# SCH_UART-HMI-OLED_2026-03-10.net
KiCad netlist of a schematic drawn in EasyEDA
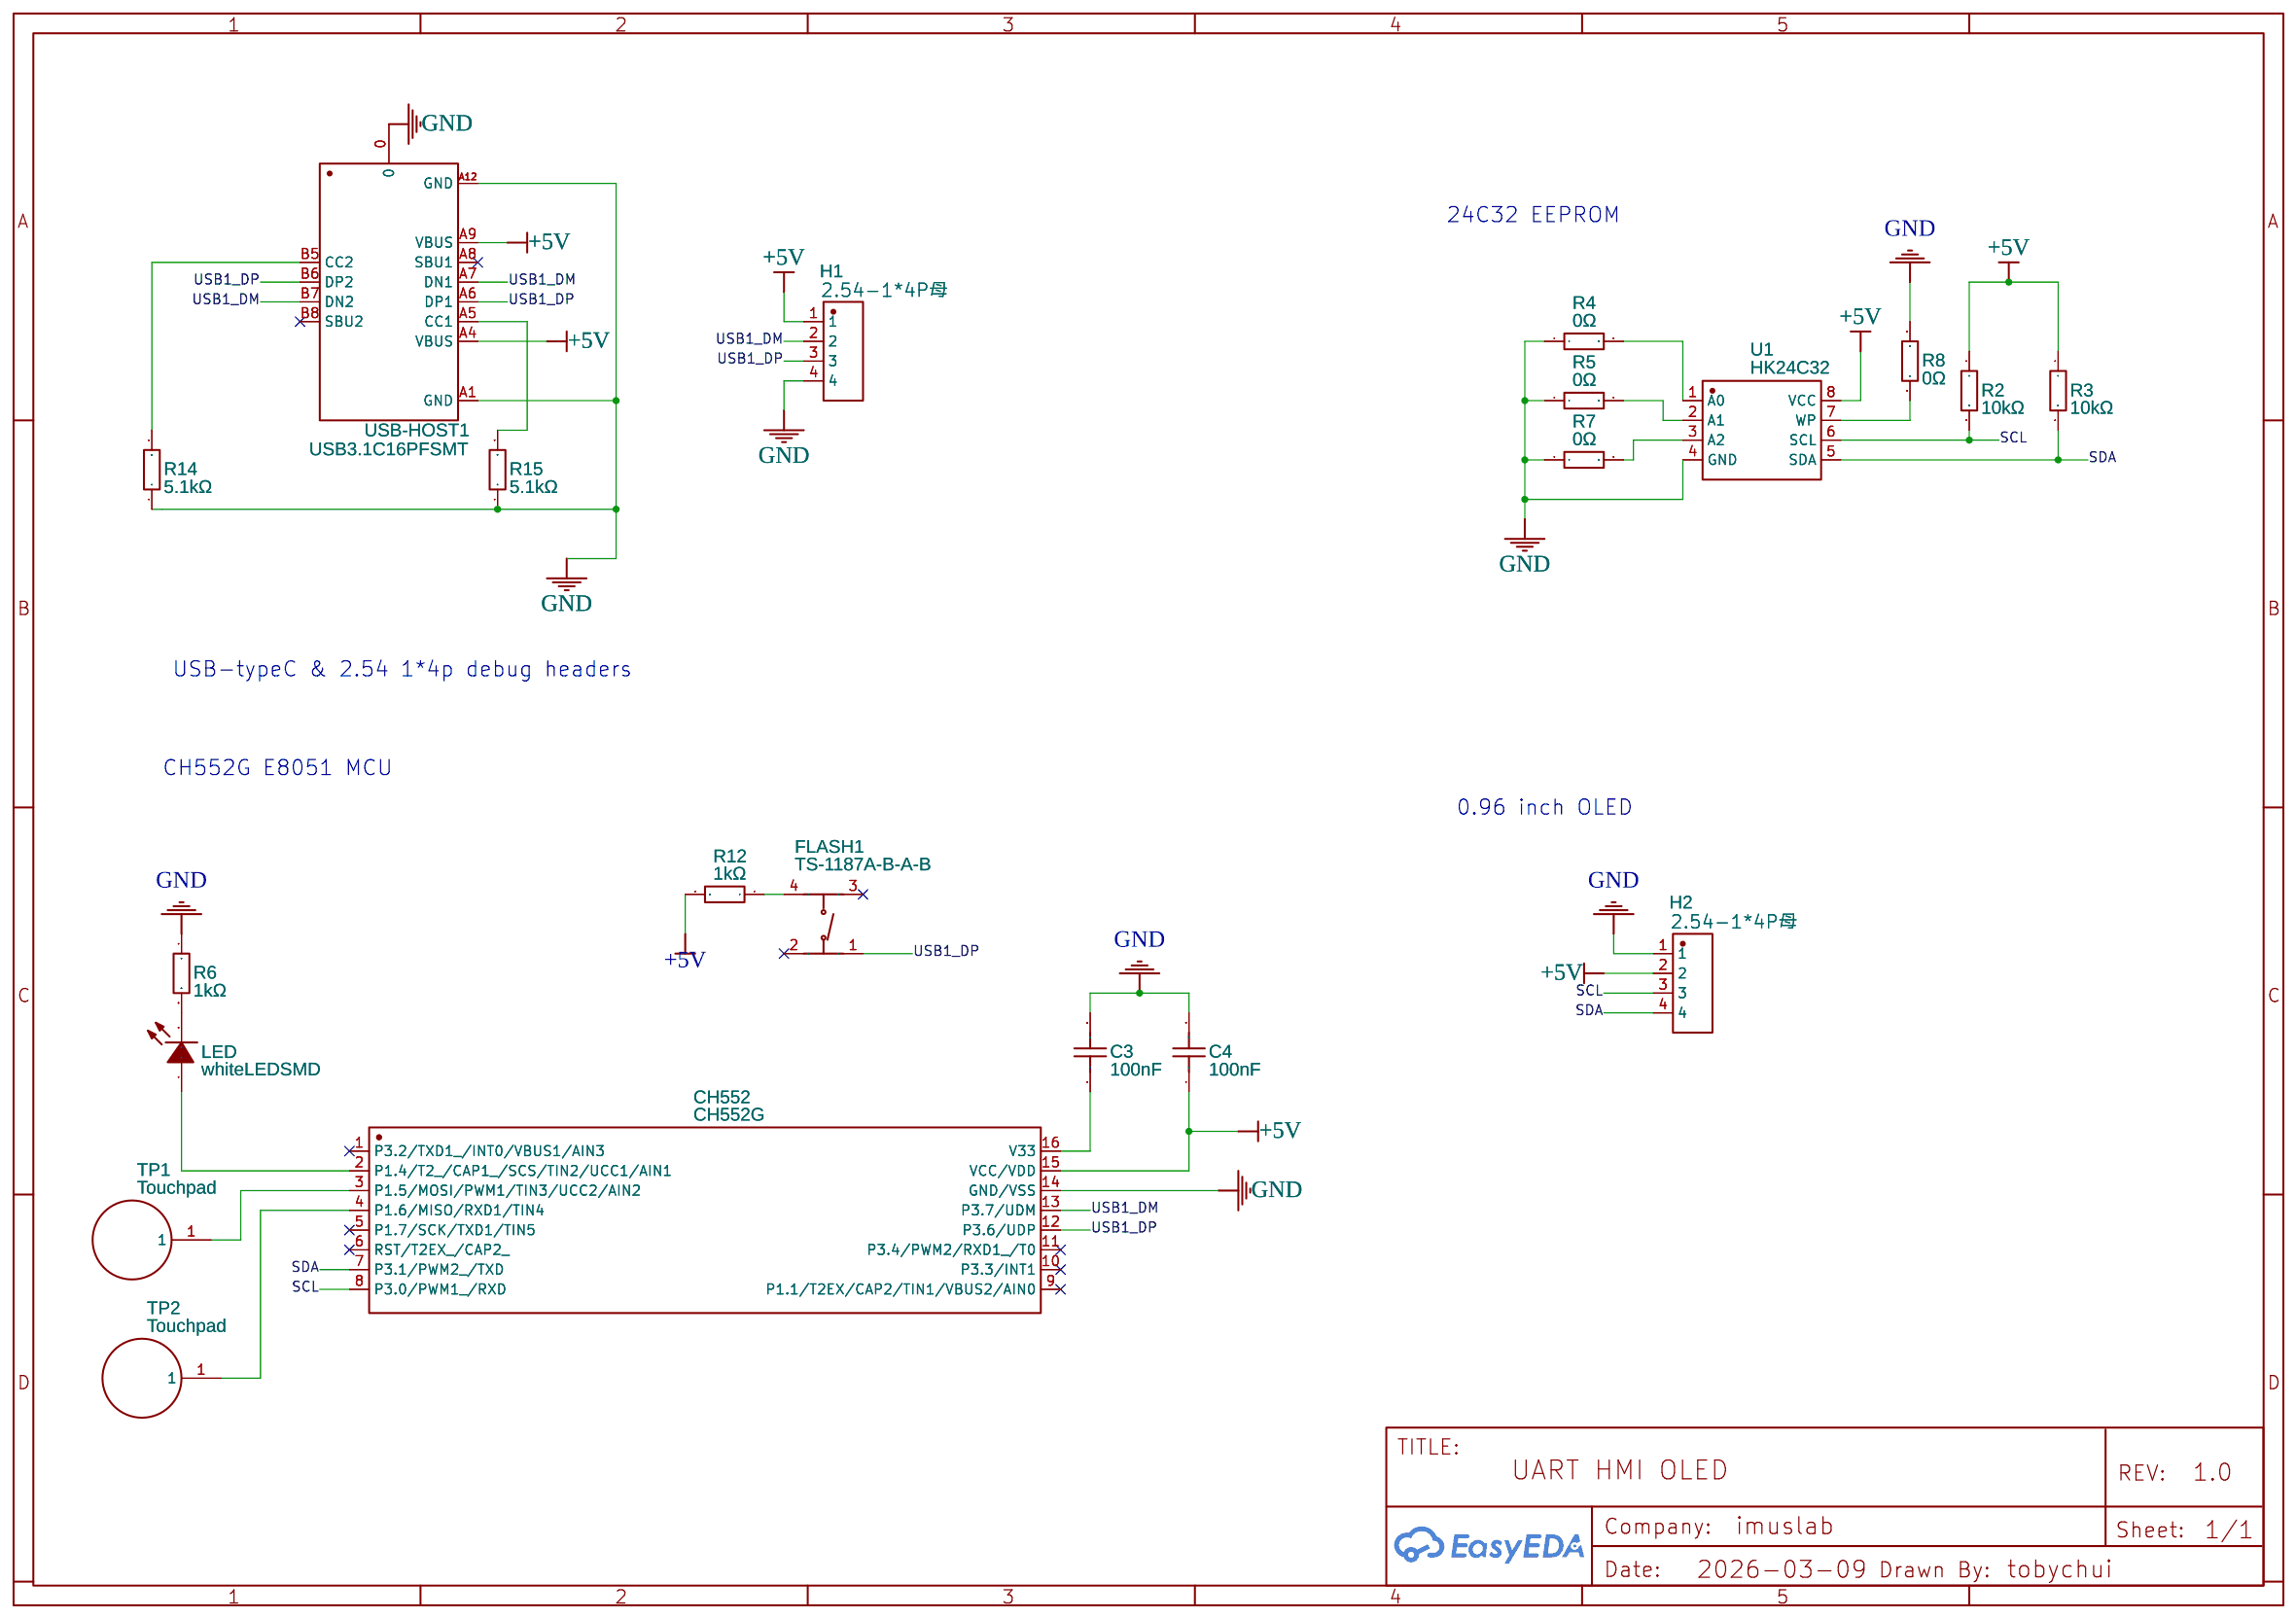
[diagram p0: schematic sheet]

(export (version "E")
  (design (tool "Eeschema 10.0.6"))
  (components
    (comp (ref "C3")
      (value "100nF")
      (fields
        (field (name "Manufacturer Part") "CC0805KRX7R9BB104")
        (field (name "Manufacturer") "YAGEO(国巨)")
      )
      (libsource (lib "") (part "CC0805KRX7R9BB104"))
    )
    (comp (ref "C4")
      (value "100nF")
      (fields
        (field (name "Manufacturer Part") "CC0805KRX7R9BB104")
        (field (name "Manufacturer") "YAGEO(国巨)")
      )
      (libsource (lib "") (part "CC0805KRX7R9BB104"))
    )
    (comp (ref "CH552")
      (value "CH552G")
      (fields (field (name "Manufacturer") "WCH(南京沁恒)"))
      (libsource (lib "") (part "CH552G"))
    )
    (comp (ref "FLASH1")
      (value "TS-1187A-B-A-B")
      (fields (field (name "Manufacturer") "XKB Connectivity(中国星坤)"))
      (libsource (lib "") (part "TS-1187A-B-A-B"))
    )
    (comp (ref "H1")
      (value "2.54-1*4P母")
      (fields (field (name "Manufacturer") "BOOMELE(博穆精密)"))
      (libsource (lib "") (part "2.54-1*4P母"))
    )
    (comp (ref "H2")
      (value "2.54-1*4P母")
      (fields (field (name "Manufacturer") "BOOMELE(博穆精密)"))
      (libsource (lib "") (part "2.54-1*4P母"))
    )
    (comp (ref "LED")
      (value "whiteLEDSMD")
      (fields (field (name "Manufacturer Part") "KT-0805W") (field (name "Manufacturer") "KENTO"))
      (libsource (lib "") (part "whiteLEDSMD"))
    )
    (comp (ref "R2")
      (value "10kΩ")
      (fields
        (field (name "Manufacturer Part") "0805W8F1002T5E")
        (field (name "Manufacturer") "UNI-ROYAL(厚声)")
      )
      (libsource (lib "") (part "0805W8F1002T5E"))
    )
    (comp (ref "R3")
      (value "10kΩ")
      (fields
        (field (name "Manufacturer Part") "0805W8F1002T5E")
        (field (name "Manufacturer") "UNI-ROYAL(厚声)")
      )
      (libsource (lib "") (part "0805W8F1002T5E"))
    )
    (comp (ref "R4")
      (value "0Ω")
      (fields
        (field (name "Manufacturer Part") "0805W8F0000T5E")
        (field (name "Manufacturer") "UNI-ROYAL(厚声)")
      )
      (libsource (lib "") (part "0805W8F0000T5E"))
    )
    (comp (ref "R5")
      (value "0Ω")
      (fields
        (field (name "Manufacturer Part") "0805W8F0000T5E")
        (field (name "Manufacturer") "UNI-ROYAL(厚声)")
      )
      (libsource (lib "") (part "0805W8F0000T5E"))
    )
    (comp (ref "R6")
      (value "1kΩ")
      (fields
        (field (name "Manufacturer Part") "0805W8F1001T5E")
        (field (name "Manufacturer") "UNI-ROYAL(厚声)")
      )
      (libsource (lib "") (part "0805W8F1001T5E_1"))
    )
    (comp (ref "R7")
      (value "0Ω")
      (fields
        (field (name "Manufacturer Part") "0805W8F0000T5E")
        (field (name "Manufacturer") "UNI-ROYAL(厚声)")
      )
      (libsource (lib "") (part "0805W8F0000T5E"))
    )
    (comp (ref "R8")
      (value "0Ω")
      (fields
        (field (name "Manufacturer Part") "0805W8F0000T5E")
        (field (name "Manufacturer") "UNI-ROYAL(厚声)")
      )
      (libsource (lib "") (part "0805W8F0000T5E_1"))
    )
    (comp (ref "R12")
      (value "1kΩ")
      (fields
        (field (name "Manufacturer Part") "0805W8F1001T5E")
        (field (name "Manufacturer") "UNI-ROYAL(厚声)")
      )
      (libsource (lib "") (part "0805W8F1001T5E"))
    )
    (comp (ref "R14")
      (value "5.1kΩ")
      (fields
        (field (name "Manufacturer Part") "0805W8F5101T5E")
        (field (name "Manufacturer") "UNI-ROYAL(厚声)")
      )
      (libsource (lib "") (part "0805W8F5101T5E"))
    )
    (comp (ref "R15")
      (value "5.1kΩ")
      (fields
        (field (name "Manufacturer Part") "0805W8F5101T5E")
        (field (name "Manufacturer") "UNI-ROYAL(厚声)")
      )
      (libsource (lib "") (part "0805W8F5101T5E"))
    )
    (comp (ref "TP1") (value "Touchpad") (libsource (lib "") (part "Touchpad")))
    (comp (ref "TP2") (value "Touchpad") (libsource (lib "") (part "Touchpad")))
    (comp (ref "U1")
      (value "HK24C32")
      (fields (field (name "Manufacturer") "HK(航顺)"))
      (libsource (lib "") (part "HK24C32"))
    )
    (comp (ref "USB-HOST1")
      (value "USB3.1C16PFSMT")
      (fields (field (name "Manufacturer Part") "918-418K2023S40001") (field (name "Manufacturer") "精拓金"))
      (libsource (lib "") (part "USB3.1C16PFSMT"))
    )
  )
  (nets
    (net (code "1") (name "+5V") (class "Default")
      (node (ref "C4") (pin "1") (pinfunction "1_1") (pintype "unspecified"))
      (node (ref "CH552") (pin "15") (pinfunction "VCC/VDD_15") (pintype "unspecified"))
      (node (ref "H1") (pin "1") (pinfunction "1_1") (pintype "unspecified"))
      (node (ref "H2") (pin "2") (pinfunction "2_2") (pintype "unspecified"))
      (node (ref "R12") (pin "2") (pinfunction "2_2") (pintype "input"))
      (node (ref "R2") (pin "1") (pinfunction "1_1") (pintype "input"))
      (node (ref "R3") (pin "1") (pinfunction "1_1") (pintype "input"))
      (node (ref "U1") (pin "8") (pinfunction "VCC_8") (pintype "unspecified"))
      (node (ref "USB-HOST1") (pin "A4") (pinfunction "VBUS_A4") (pintype "unspecified"))
      (node (ref "USB-HOST1") (pin "A9") (pinfunction "VBUS_A9") (pintype "unspecified"))
    )
    (net (code "2") (name "/SCL") (class "Default")
      (node (ref "CH552") (pin "8") (pinfunction "P3.0/PWM1_/RXD_8") (pintype "unspecified"))
      (node (ref "H2") (pin "3") (pinfunction "3_3") (pintype "unspecified"))
      (node (ref "R2") (pin "2") (pinfunction "2_2") (pintype "input"))
      (node (ref "U1") (pin "6") (pinfunction "SCL_6") (pintype "unspecified"))
    )
    (net (code "3") (name "/SDA") (class "Default")
      (node (ref "CH552") (pin "7") (pinfunction "P3.1/PWM2_/TXD_7") (pintype "unspecified"))
      (node (ref "H2") (pin "4") (pinfunction "4_4") (pintype "unspecified"))
      (node (ref "R3") (pin "2") (pinfunction "2_2") (pintype "input"))
      (node (ref "U1") (pin "5") (pinfunction "SDA_5") (pintype "unspecified"))
    )
    (net (code "4") (name "/USB1_DM") (class "Default")
      (node (ref "CH552") (pin "13") (pinfunction "P3.7/UDM_13") (pintype "unspecified"))
      (node (ref "H1") (pin "2") (pinfunction "2_2") (pintype "unspecified"))
      (node (ref "USB-HOST1") (pin "A7") (pinfunction "DN1_A7") (pintype "unspecified"))
      (node (ref "USB-HOST1") (pin "B7") (pinfunction "DN2_B7") (pintype "unspecified"))
    )
    (net (code "5") (name "/USB1_DP") (class "Default")
      (node (ref "CH552") (pin "12") (pinfunction "P3.6/UDP_12") (pintype "unspecified"))
      (node (ref "FLASH1") (pin "1") (pinfunction "A_1") (pintype "unspecified"))
      (node (ref "H1") (pin "3") (pinfunction "3_3") (pintype "unspecified"))
      (node (ref "USB-HOST1") (pin "A6") (pinfunction "DP1_A6") (pintype "unspecified"))
      (node (ref "USB-HOST1") (pin "B6") (pinfunction "DP2_B6") (pintype "unspecified"))
    )
    (net (code "6") (name "GND") (class "Default")
      (node (ref "C3") (pin "2") (pinfunction "2_2") (pintype "unspecified"))
      (node (ref "C4") (pin "2") (pinfunction "2_2") (pintype "unspecified"))
      (node (ref "CH552") (pin "14") (pinfunction "GND/VSS_14") (pintype "unspecified"))
      (node (ref "H1") (pin "4") (pinfunction "4_4") (pintype "unspecified"))
      (node (ref "H2") (pin "1") (pinfunction "1_1") (pintype "unspecified"))
      (node (ref "R14") (pin "1") (pinfunction "1_1") (pintype "input"))
      (node (ref "R15") (pin "1") (pinfunction "1_1") (pintype "input"))
      (node (ref "R4") (pin "1") (pinfunction "1_1") (pintype "input"))
      (node (ref "R5") (pin "1") (pinfunction "1_1") (pintype "input"))
      (node (ref "R6") (pin "1") (pinfunction "1_1") (pintype "input"))
      (node (ref "R7") (pin "1") (pinfunction "1_1") (pintype "input"))
      (node (ref "R8") (pin "2") (pinfunction "2_2") (pintype "input"))
      (node (ref "U1") (pin "4") (pinfunction "GND_4") (pintype "unspecified"))
      (node (ref "USB-HOST1") (pin "0") (pinfunction "0_0") (pintype "unspecified"))
      (node (ref "USB-HOST1") (pin "A1") (pinfunction "GND_A1") (pintype "unspecified"))
      (node (ref "USB-HOST1") (pin "A12") (pinfunction "GND_A12") (pintype "unspecified"))
    )
    (net (code "7") (name "Net-(CH552-P1.4{slash}T2_{slash}CAP1_{slash}SCS{slash}TIN2{slash}UCC1{slash}AIN1)") (class "Default")
      (node (ref "CH552") (pin "2") (pinfunction "P1.4/T2_/CAP1_/SCS/TIN2/UCC1/AIN1_2") (pintype "unspecified"))
      (node (ref "LED") (pin "1") (pinfunction "A_1") (pintype "unspecified"))
    )
    (net (code "8") (name "Net-(CH552-P1.5{slash}MOSI{slash}PWM1{slash}TIN3{slash}UCC2{slash}AIN2)") (class "Default")
      (node (ref "CH552") (pin "3") (pinfunction "P1.5/MOSI/PWM1/TIN3/UCC2/AIN2_3") (pintype "unspecified"))
      (node (ref "TP1") (pin "1") (pinfunction "1_1") (pintype "unspecified"))
    )
    (net (code "9") (name "Net-(CH552-P1.6{slash}MISO{slash}RXD1{slash}TIN4)") (class "Default")
      (node (ref "CH552") (pin "4") (pinfunction "P1.6/MISO/RXD1/TIN4_4") (pintype "unspecified"))
      (node (ref "TP2") (pin "1") (pinfunction "1_1") (pintype "unspecified"))
    )
    (net (code "10") (name "Net-(CH552-V33)") (class "Default")
      (node (ref "C3") (pin "1") (pinfunction "1_1") (pintype "unspecified"))
      (node (ref "CH552") (pin "16") (pinfunction "V33_16") (pintype "unspecified"))
    )
    (net (code "11") (name "Net-(FLASH1-D)") (class "Default")
      (node (ref "FLASH1") (pin "4") (pinfunction "D_4") (pintype "unspecified"))
      (node (ref "R12") (pin "1") (pinfunction "1_1") (pintype "input"))
    )
    (net (code "12") (name "Net-(LED-K)") (class "Default")
      (node (ref "LED") (pin "2") (pinfunction "K_2") (pintype "unspecified"))
      (node (ref "R6") (pin "2") (pinfunction "2_2") (pintype "input"))
    )
    (net (code "13") (name "Net-(U1-A0)") (class "Default")
      (node (ref "R4") (pin "2") (pinfunction "2_2") (pintype "input"))
      (node (ref "U1") (pin "1") (pinfunction "A0_1") (pintype "unspecified"))
    )
    (net (code "14") (name "Net-(U1-A1)") (class "Default")
      (node (ref "R5") (pin "2") (pinfunction "2_2") (pintype "input"))
      (node (ref "U1") (pin "2") (pinfunction "A1_2") (pintype "unspecified"))
    )
    (net (code "15") (name "Net-(U1-A2)") (class "Default")
      (node (ref "R7") (pin "2") (pinfunction "2_2") (pintype "input"))
      (node (ref "U1") (pin "3") (pinfunction "A2_3") (pintype "unspecified"))
    )
    (net (code "16") (name "Net-(U1-WP)") (class "Default")
      (node (ref "R8") (pin "1") (pinfunction "1_1") (pintype "input"))
      (node (ref "U1") (pin "7") (pinfunction "WP_7") (pintype "unspecified"))
    )
    (net (code "17") (name "Net-(USB-HOST1-CC1)") (class "Default")
      (node (ref "R15") (pin "2") (pinfunction "2_2") (pintype "input"))
      (node (ref "USB-HOST1") (pin "A5") (pinfunction "CC1_A5") (pintype "unspecified"))
    )
    (net (code "18") (name "Net-(USB-HOST1-CC2)") (class "Default")
      (node (ref "R14") (pin "2") (pinfunction "2_2") (pintype "input"))
      (node (ref "USB-HOST1") (pin "B5") (pinfunction "CC2_B5") (pintype "unspecified"))
    )
    (net (code "19") (name "unconnected-(CH552-P1.1{slash}T2EX{slash}CAP2{slash}TIN1{slash}VBUS2{slash}AIN0-Pad9)") (class "Default")
      (node (ref "CH552") (pin "9") (pinfunction "P1.1/T2EX/CAP2/TIN1/VBUS2/AIN0_9") (pintype "unspecified+no_connect"))
    )
    (net (code "20") (name "unconnected-(CH552-P1.7{slash}SCK{slash}TXD1{slash}TIN5-Pad5)") (class "Default")
      (node (ref "CH552") (pin "5") (pinfunction "P1.7/SCK/TXD1/TIN5_5") (pintype "unspecified+no_connect"))
    )
    (net (code "21") (name "unconnected-(CH552-P3.2{slash}TXD1_{slash}INT0{slash}VBUS1{slash}AIN3-Pad1)") (class "Default")
      (node (ref "CH552") (pin "1") (pinfunction "P3.2/TXD1_/INT0/VBUS1/AIN3_1") (pintype "unspecified+no_connect"))
    )
    (net (code "22") (name "unconnected-(CH552-P3.3{slash}INT1-Pad10)") (class "Default")
      (node (ref "CH552") (pin "10") (pinfunction "P3.3/INT1_10") (pintype "unspecified+no_connect"))
    )
    (net (code "23") (name "unconnected-(CH552-P3.4{slash}PWM2{slash}RXD1_{slash}T0-Pad11)") (class "Default")
      (node (ref "CH552") (pin "11") (pinfunction "P3.4/PWM2/RXD1_/T0_11") (pintype "unspecified+no_connect"))
    )
    (net (code "24") (name "unconnected-(CH552-RST{slash}T2EX_{slash}CAP2_-Pad6)") (class "Default")
      (node (ref "CH552") (pin "6") (pinfunction "RST/T2EX_/CAP2__6") (pintype "unspecified+no_connect"))
    )
    (net (code "25") (name "unconnected-(FLASH1-B-Pad2)") (class "Default")
      (node (ref "FLASH1") (pin "2") (pinfunction "B_2") (pintype "unspecified+no_connect"))
    )
    (net (code "26") (name "unconnected-(FLASH1-C-Pad3)") (class "Default")
      (node (ref "FLASH1") (pin "3") (pinfunction "C_3") (pintype "unspecified+no_connect"))
    )
    (net (code "27") (name "unconnected-(USB-HOST1-SBU1-PadA8)") (class "Default")
      (node (ref "USB-HOST1") (pin "A8") (pinfunction "SBU1_A8") (pintype "unspecified+no_connect"))
    )
    (net (code "28") (name "unconnected-(USB-HOST1-SBU2-PadB8)") (class "Default")
      (node (ref "USB-HOST1") (pin "B8") (pinfunction "SBU2_B8") (pintype "unspecified+no_connect"))
    )
  )
)
